# power.net
KiCad netlist of a schematic drawn in Altium Designer
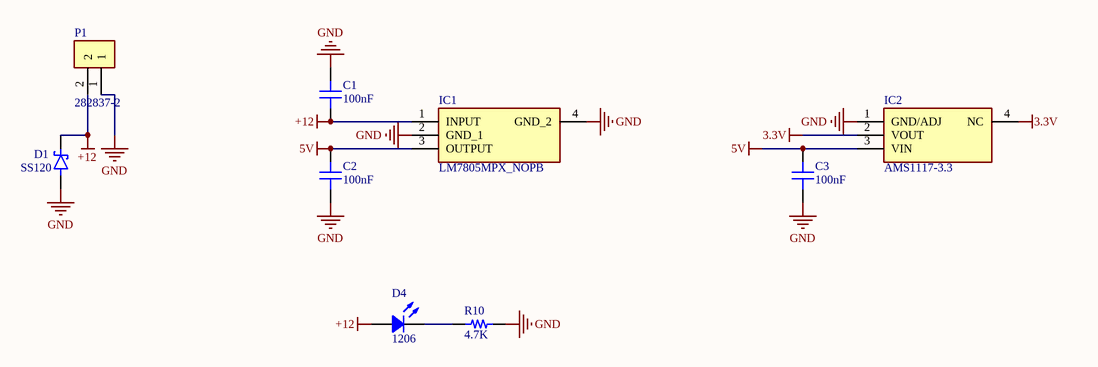
[diagram p0: power.SchDoc]

(export (version "E")
  (design (tool "Eeschema 10.0.6"))
  (components
    (comp (ref "C1")
      (value "100nF")
      (footprint "CAP 1206_3216 - 0.8MM")
      (description "CAP CER 1000PF 200V X7R 1206")
      (fields (field (name "PART NUMBER") "MM062C102KCZ2A") (field (name "MANUFACTURER") "AVX Corporation"))
      (libsource (lib "Celestial Altium Library - altium_library") (part "Capacitor"))
    )
    (comp (ref "C2")
      (value "100nF")
      (footprint "CAP 1206_3216 - 0.8MM")
      (description "CAP CER 1000PF 200V X7R 1206")
      (fields (field (name "PART NUMBER") "MM062C102KCZ2A") (field (name "MANUFACTURER") "AVX Corporation"))
      (libsource (lib "Celestial Altium Library - altium_library") (part "Capacitor"))
    )
    (comp (ref "C3")
      (value "100nF")
      (footprint "CAP 1206_3216 - 0.8MM")
      (description "CAP CER 1000PF 200V X7R 1206")
      (fields (field (name "PART NUMBER") "MM062C102KCZ2A") (field (name "MANUFACTURER") "AVX Corporation"))
      (libsource (lib "Celestial Altium Library - altium_library") (part "Capacitor"))
    )
    (comp (ref "D1")
      (value "SS120")
      (footprint "DIOM4325X250N")
      (description "1A, 200V, Schottky Rectifier")
      (fields (field (name "MF") "Taiwan Semiconductor"))
      (libsource (lib "SS120") (part "SS120"))
    )
    (comp (ref "D4")
      (value "1206")
      (footprint "LED 1206_3216 YELLOW")
      (description "LED YELLOW CLEAR 2SMD")
      (fields
        (field (name "PART NUMBER") "25-21UYC/S530-A2/TR8")
        (field (name "MANUFACTURER") "Everlight Electronics Co Ltd")
      )
      (libsource (lib "Celestial Altium Library - altium_library") (part "LED"))
    )
    (comp (ref "IC1")
      (value "LM7805MPX_NOPB")
      (footprint "SamacSys:SOT230P700X180-4N")
      (description "Integrated Circuit")
      (fields
        (field (name "MANUFACTURER_PART_NUMBER") "LM7805MPX/NOPB")
        (field (name "MOUSER PART NUMBER") "595-LM7805MPX/NOPB")
      )
      (libsource (lib "*") (part "LM7805MPX_NOPB"))
    )
    (comp (ref "IC2")
      (value "AMS1117-3.3")
      (footprint "SamacSys:SOT229P700X180-4N")
      (description "Integrated Circuit")
      (libsource (lib "*") (part "AMS1117-3.3"))
    )
    (comp (ref "P1")
      (value "282837-2")
      (footprint "TE_282837-2")
      (fields (field (name "MF") "TE Connectivity"))
      (libsource (lib "connector") (part "282837-2"))
    )
    (comp (ref "R10")
      (value "4.7K")
      (footprint "RES 1206_3216")
      (description "RES SMD 61.9K OHM 1% 1/4W 1206")
      (fields (field (name "PART NUMBER") "CRCW120661K9FKEA") (field (name "MANUFACTURER") "Vishay Dale"))
      (libsource (lib "Celestial Altium Library - altium_library") (part "Resistor"))
    )
  )
  (nets
    (net (code "1") (name "+12") (class "Default")
      (node (ref "C1") (pin "1") (pinfunction "1_1") (pintype "passive"))
      (node (ref "D1") (pin "C") (pinfunction "K_C") (pintype "passive"))
      (node (ref "D4") (pin "1") (pinfunction "1_1") (pintype "passive"))
      (node (ref "IC1") (pin "1") (pinfunction "INPUT_1") (pintype "passive"))
      (node (ref "P1") (pin "2") (pinfunction "2_2") (pintype "passive"))
    )
    (net (code "2") (name "3.3V") (class "Default")
      (node (ref "IC2") (pin "2") (pinfunction "VOUT_2") (pintype "passive"))
      (node (ref "IC2") (pin "4") (pinfunction "NC_4") (pintype "passive"))
    )
    (net (code "3") (name "5V") (class "Default")
      (node (ref "C2") (pin "2") (pinfunction "2_2") (pintype "passive"))
      (node (ref "C3") (pin "2") (pinfunction "2_2") (pintype "passive"))
      (node (ref "IC1") (pin "3") (pinfunction "OUTPUT_3") (pintype "passive"))
      (node (ref "IC2") (pin "3") (pinfunction "VIN_3") (pintype "passive"))
    )
    (net (code "4") (name "GND") (class "Default")
      (node (ref "C1") (pin "2") (pinfunction "2_2") (pintype "passive"))
      (node (ref "C2") (pin "1") (pinfunction "1_1") (pintype "passive"))
      (node (ref "C3") (pin "1") (pinfunction "1_1") (pintype "passive"))
      (node (ref "D1") (pin "A") (pinfunction "A_A") (pintype "passive"))
      (node (ref "IC1") (pin "2") (pinfunction "GND_1_2") (pintype "passive"))
      (node (ref "IC1") (pin "4") (pinfunction "GND_2_4") (pintype "passive"))
      (node (ref "IC2") (pin "1") (pinfunction "GND/ADJ_1") (pintype "passive"))
      (node (ref "P1") (pin "1") (pinfunction "1_1") (pintype "passive"))
      (node (ref "R10") (pin "1") (pinfunction "1_1") (pintype "passive"))
    )
    (net (code "5") (name "Net-(D4-Pad2)") (class "Default")
      (node (ref "D4") (pin "2") (pinfunction "2_2") (pintype "passive"))
      (node (ref "R10") (pin "2") (pinfunction "2_2") (pintype "passive"))
    )
  )
)
